# schema_v1.net
KiCad netlist of a schematic drawn in EAGLE
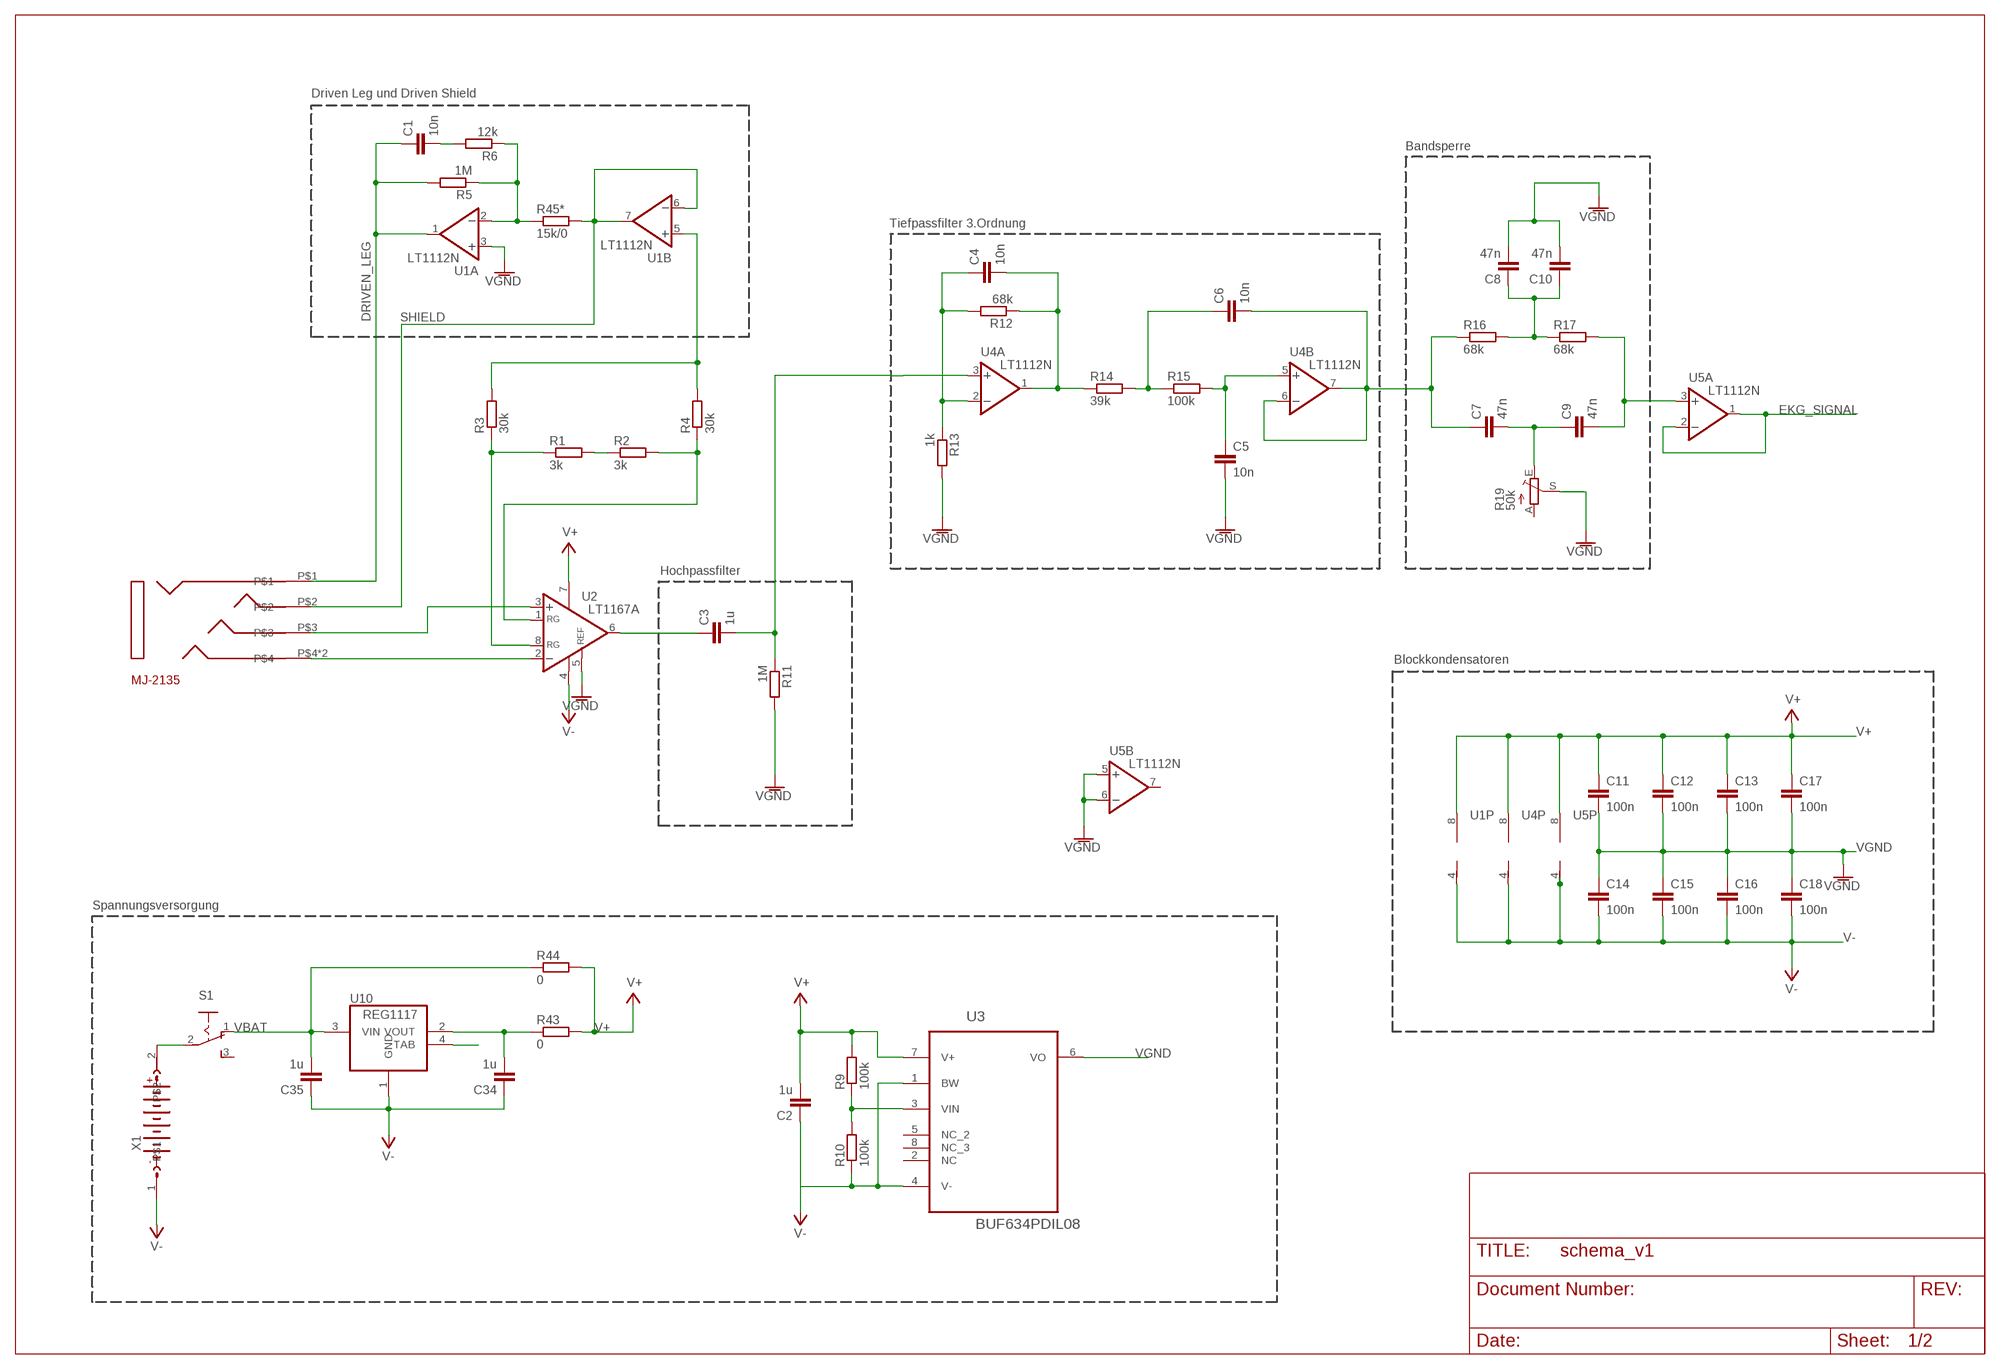
[diagram p0: schematic, sheet 1]
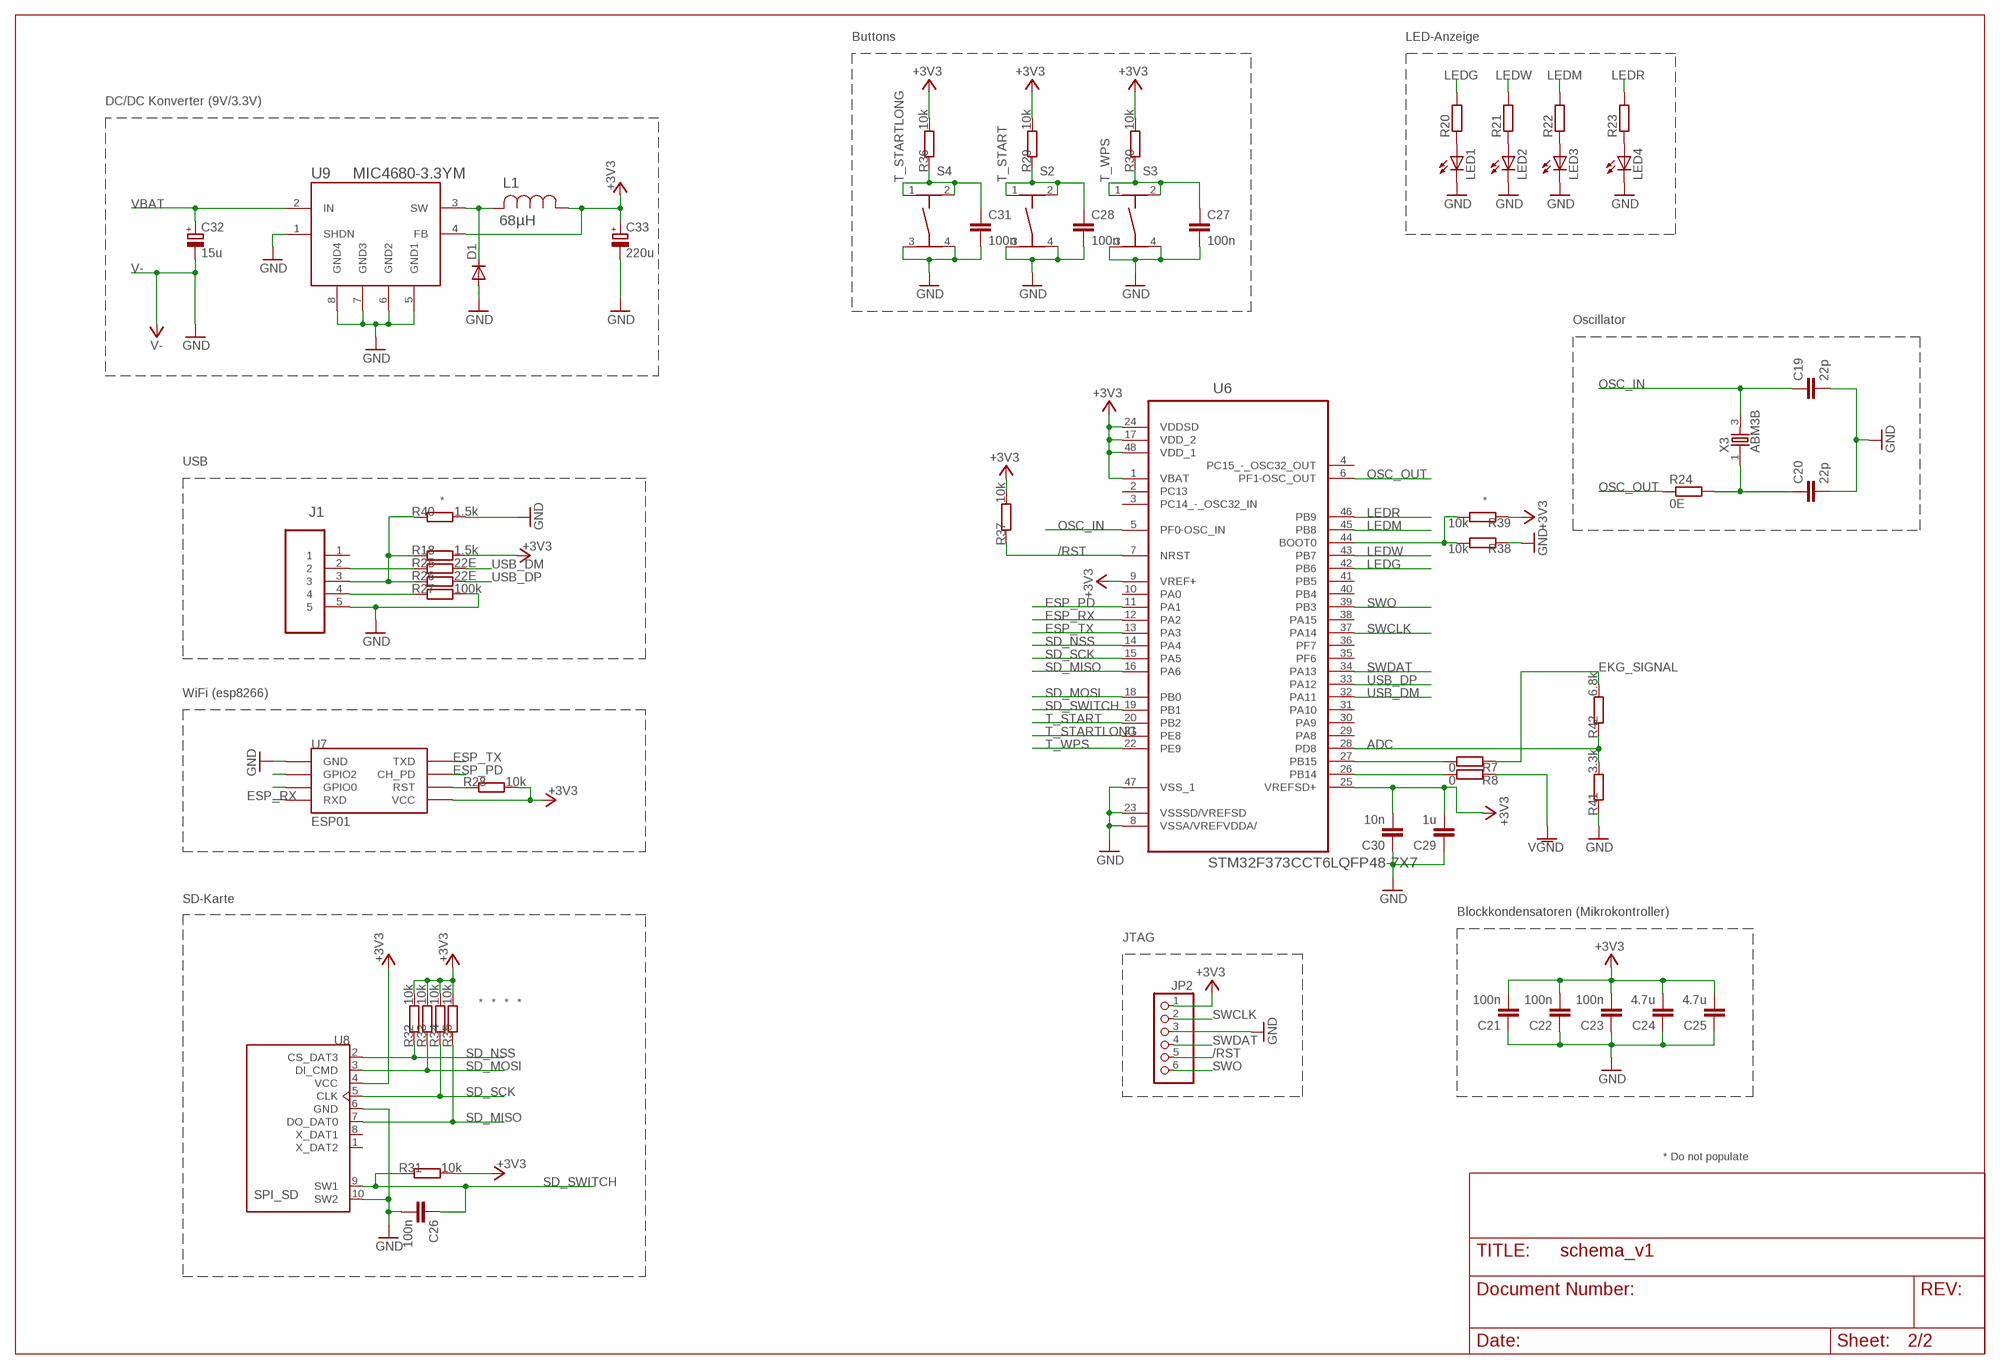
[diagram p1: schematic, sheet 2]

(export (version "E")
  (design (tool "Eeschema 10.0.6"))
  (components
    (comp (ref "C1")
      (value "10n")
      (footprint "eagle-import:C0805")
      (libsource (lib "eagle-import") (part "C-EUC0805"))
    )
    (comp (ref "C2")
      (value "1u")
      (footprint "eagle-import:C0805")
      (libsource (lib "eagle-import") (part "C-EUC0805"))
    )
    (comp (ref "C3")
      (value "1u")
      (footprint "eagle-import:C0805")
      (libsource (lib "eagle-import") (part "C-EUC0805"))
    )
    (comp (ref "C4")
      (value "10n")
      (footprint "eagle-import:C0805")
      (libsource (lib "eagle-import") (part "C-EUC0805"))
    )
    (comp (ref "C5")
      (value "10n")
      (footprint "eagle-import:C0805")
      (libsource (lib "eagle-import") (part "C-EUC0805"))
    )
    (comp (ref "C6")
      (value "10n")
      (footprint "eagle-import:C0805")
      (libsource (lib "eagle-import") (part "C-EUC0805"))
    )
    (comp (ref "C7")
      (value "47n")
      (footprint "eagle-import:C0805")
      (libsource (lib "eagle-import") (part "C-EUC0805"))
    )
    (comp (ref "C8")
      (value "47n")
      (footprint "eagle-import:C0805")
      (libsource (lib "eagle-import") (part "C-EUC0805"))
    )
    (comp (ref "C9")
      (value "47n")
      (footprint "eagle-import:C0805")
      (libsource (lib "eagle-import") (part "C-EUC0805"))
    )
    (comp (ref "C10")
      (value "47n")
      (footprint "eagle-import:C0805")
      (libsource (lib "eagle-import") (part "C-EUC0805"))
    )
    (comp (ref "C11")
      (value "100n")
      (footprint "eagle-import:C0805")
      (libsource (lib "eagle-import") (part "C-EUC0805"))
    )
    (comp (ref "C12")
      (value "100n")
      (footprint "eagle-import:C0805")
      (libsource (lib "eagle-import") (part "C-EUC0805"))
    )
    (comp (ref "C13")
      (value "100n")
      (footprint "eagle-import:C0805")
      (libsource (lib "eagle-import") (part "C-EUC0805"))
    )
    (comp (ref "C14")
      (value "100n")
      (footprint "eagle-import:C0805")
      (libsource (lib "eagle-import") (part "C-EUC0805"))
    )
    (comp (ref "C15")
      (value "100n")
      (footprint "eagle-import:C0805")
      (libsource (lib "eagle-import") (part "C-EUC0805"))
    )
    (comp (ref "C16")
      (value "100n")
      (footprint "eagle-import:C0805")
      (libsource (lib "eagle-import") (part "C-EUC0805"))
    )
    (comp (ref "C17")
      (value "100n")
      (footprint "eagle-import:C0805")
      (libsource (lib "eagle-import") (part "C-EUC0805"))
    )
    (comp (ref "C18")
      (value "100n")
      (footprint "eagle-import:C0805")
      (libsource (lib "eagle-import") (part "C-EUC0805"))
    )
    (comp (ref "C34")
      (value "1u")
      (footprint "eagle-import:C0805")
      (libsource (lib "eagle-import") (part "C-EUC0805"))
    )
    (comp (ref "C35")
      (value "1u")
      (footprint "eagle-import:C0805")
      (libsource (lib "eagle-import") (part "C-EUC0805"))
    )
    (comp (ref "R1")
      (value "3k")
      (footprint "eagle-import:M0805")
      (libsource (lib "eagle-import") (part "R-EU_M0805"))
    )
    (comp (ref "R2")
      (value "3k")
      (footprint "eagle-import:M0805")
      (libsource (lib "eagle-import") (part "R-EU_M0805"))
    )
    (comp (ref "R3")
      (value "30k")
      (footprint "eagle-import:M0805")
      (libsource (lib "eagle-import") (part "R-EU_M0805"))
    )
    (comp (ref "R4")
      (value "30k")
      (footprint "eagle-import:M0805")
      (libsource (lib "eagle-import") (part "R-EU_M0805"))
    )
    (comp (ref "R5")
      (value "1M")
      (footprint "eagle-import:M0805")
      (libsource (lib "eagle-import") (part "R-EU_M0805"))
    )
    (comp (ref "R6")
      (value "12k")
      (footprint "eagle-import:M0805")
      (libsource (lib "eagle-import") (part "R-EU_M0805"))
    )
    (comp (ref "R9")
      (value "100k")
      (footprint "eagle-import:M0805")
      (libsource (lib "eagle-import") (part "R-EU_M0805"))
    )
    (comp (ref "R10")
      (value "100k")
      (footprint "eagle-import:M0805")
      (libsource (lib "eagle-import") (part "R-EU_M0805"))
    )
    (comp (ref "R11")
      (value "1M")
      (footprint "eagle-import:M0805")
      (libsource (lib "eagle-import") (part "R-EU_M0805"))
    )
    (comp (ref "R12")
      (value "68k")
      (footprint "eagle-import:M0805")
      (libsource (lib "eagle-import") (part "R-EU_M0805"))
    )
    (comp (ref "R13")
      (value "1k")
      (footprint "eagle-import:M0805")
      (libsource (lib "eagle-import") (part "R-EU_M0805"))
    )
    (comp (ref "R14")
      (value "39k")
      (footprint "eagle-import:M0805")
      (libsource (lib "eagle-import") (part "R-EU_M0805"))
    )
    (comp (ref "R15")
      (value "100k")
      (footprint "eagle-import:M0805")
      (libsource (lib "eagle-import") (part "R-EU_M0805"))
    )
    (comp (ref "R16")
      (value "68k")
      (footprint "eagle-import:M0805")
      (libsource (lib "eagle-import") (part "R-EU_M0805"))
    )
    (comp (ref "R17")
      (value "68k")
      (footprint "eagle-import:M0805")
      (libsource (lib "eagle-import") (part "R-EU_M0805"))
    )
    (comp (ref "R19")
      (value "50k")
      (footprint "eagle-import:B25P")
      (libsource (lib "eagle-import") (part "TRIM_EU-B25P"))
    )
    (comp (ref "R43")
      (value "0")
      (footprint "eagle-import:M0805")
      (libsource (lib "eagle-import") (part "R-EU_M0805"))
    )
    (comp (ref "R44")
      (value "0")
      (footprint "eagle-import:M0805")
      (libsource (lib "eagle-import") (part "R-EU_M0805"))
    )
    (comp (ref "R45*")
      (value "15k/0")
      (footprint "eagle-import:R0805")
      (libsource (lib "eagle-import") (part "R-EU_R0805"))
    )
    (comp (ref "S1")
      (value "255SB")
      (footprint "eagle-import:255SB")
      (libsource (lib "eagle-import") (part "255SB"))
    )
    (comp (ref "U1")
      (value "LT1112N")
      (footprint "eagle-import:DIL08")
      (libsource (lib "eagle-import") (part "LT1112N"))
    )
    (comp (ref "U2")
      (value "LT1167A")
      (footprint "eagle-import:DIL08")
      (libsource (lib "eagle-import") (part "LT1167A"))
    )
    (comp (ref "U3")
      (value "BUF634PDIL08")
      (footprint "eagle-import:DIL08")
      (libsource (lib "eagle-import") (part "BUF634PDIL08"))
    )
    (comp (ref "U4")
      (value "LT1112N")
      (footprint "eagle-import:DIL08")
      (libsource (lib "eagle-import") (part "LT1112N"))
    )
    (comp (ref "U5")
      (value "LT1112N")
      (footprint "eagle-import:DIL08")
      (libsource (lib "eagle-import") (part "LT1112N"))
    )
    (comp (ref "U10")
      (value "REG1117")
      (footprint "eagle-import:SOT223")
      (libsource (lib "eagle-import") (part "REG1117"))
    )
    (comp (ref "X1")
      (value "BATTERY")
      (footprint "eagle-import:1X02")
      (libsource (lib "eagle-import") (part "BATTERY"))
    )
    (comp (ref "X2")
      (value "MJ2135")
      (footprint "eagle-import:MJ-2135")
      (libsource (lib "eagle-import") (part "MJ2135"))
    )
    (comp (ref "C19")
      (value "22p")
      (footprint "eagle-import:C0805")
      (libsource (lib "eagle-import") (part "C-EUC0805"))
    )
    (comp (ref "C20")
      (value "22p")
      (footprint "eagle-import:C0805")
      (libsource (lib "eagle-import") (part "C-EUC0805"))
    )
    (comp (ref "C21")
      (value "100n")
      (footprint "eagle-import:C0805")
      (libsource (lib "eagle-import") (part "C-EUC0805"))
    )
    (comp (ref "C22")
      (value "100n")
      (footprint "eagle-import:C0805")
      (libsource (lib "eagle-import") (part "C-EUC0805"))
    )
    (comp (ref "C23")
      (value "100n")
      (footprint "eagle-import:C0805")
      (libsource (lib "eagle-import") (part "C-EUC0805"))
    )
    (comp (ref "C24")
      (value "4.7u")
      (footprint "eagle-import:C0805")
      (libsource (lib "eagle-import") (part "C-EUC0805"))
    )
    (comp (ref "C25")
      (value "4.7u")
      (footprint "eagle-import:C0805")
      (libsource (lib "eagle-import") (part "C-EUC0805"))
    )
    (comp (ref "C26")
      (value "100n")
      (footprint "eagle-import:C0805")
      (libsource (lib "eagle-import") (part "C-EUC0805"))
    )
    (comp (ref "C27")
      (value "100n")
      (footprint "eagle-import:C0805")
      (libsource (lib "eagle-import") (part "C-EUC0805"))
    )
    (comp (ref "C28")
      (value "100n")
      (footprint "eagle-import:C0805")
      (libsource (lib "eagle-import") (part "C-EUC0805"))
    )
    (comp (ref "C29")
      (value "1u")
      (footprint "eagle-import:C0805")
      (libsource (lib "eagle-import") (part "C-EUC0805"))
    )
    (comp (ref "C30")
      (value "10n")
      (footprint "eagle-import:C0805")
      (libsource (lib "eagle-import") (part "C-EUC0805"))
    )
    (comp (ref "C31")
      (value "100n")
      (footprint "eagle-import:C0805")
      (libsource (lib "eagle-import") (part "C-EUC0805"))
    )
    (comp (ref "C32")
      (value "15u")
      (footprint "eagle-import:SMC_B")
      (libsource (lib "eagle-import") (part "CPOL-EUSMCB"))
    )
    (comp (ref "C33")
      (value "220u")
      (footprint "eagle-import:SMC_E")
      (libsource (lib "eagle-import") (part "CPOL-EUSMCE"))
    )
    (comp (ref "D1")
      (value "DIODE-DO214AC")
      (footprint "eagle-import:DO214AC")
      (libsource (lib "eagle-import") (part "DIODE-DO214AC"))
    )
    (comp (ref "J1")
      (value "47346-0001")
      (footprint "eagle-import:MOLEX_47346-0001")
      (libsource (lib "eagle-import") (part "47346-0001"))
    )
    (comp (ref "JP2")
      (value "PINHD-1X6")
      (footprint "eagle-import:1X06")
      (libsource (lib "eagle-import") (part "PINHD-1X6"))
    )
    (comp (ref "L1")
      (value "68µH")
      (footprint "eagle-import:INDM1410X600N")
      (fields (field (name "MPN") "UP2B-680-R") (field (name "TOLERANCE") "±20%"))
      (libsource (lib "eagle-import") (part "UP2B-680-R"))
    )
    (comp (ref "LED1")
      (value "LED3MM")
      (footprint "eagle-import:LED3MM")
      (libsource (lib "eagle-import") (part "LED3MM"))
    )
    (comp (ref "LED2")
      (value "LED3MM")
      (footprint "eagle-import:LED3MM")
      (libsource (lib "eagle-import") (part "LED3MM"))
    )
    (comp (ref "LED3")
      (value "LED3MM")
      (footprint "eagle-import:LED3MM")
      (libsource (lib "eagle-import") (part "LED3MM"))
    )
    (comp (ref "LED4")
      (value "LED3MM")
      (footprint "eagle-import:LED3MM")
      (libsource (lib "eagle-import") (part "LED3MM"))
    )
    (comp (ref "R7")
      (value "0")
      (footprint "eagle-import:R0805")
      (libsource (lib "eagle-import") (part "R-EU_R0805"))
    )
    (comp (ref "R8")
      (value "0")
      (footprint "eagle-import:R0805")
      (libsource (lib "eagle-import") (part "R-EU_R0805"))
    )
    (comp (ref "R18")
      (value "1.5k")
      (footprint "eagle-import:R0805")
      (libsource (lib "eagle-import") (part "R-EU_R0805"))
    )
    (comp (ref "R20")
      (value "R-EU_R0805")
      (footprint "eagle-import:R0805")
      (libsource (lib "eagle-import") (part "R-EU_R0805"))
    )
    (comp (ref "R21")
      (value "R-EU_R0805")
      (footprint "eagle-import:R0805")
      (libsource (lib "eagle-import") (part "R-EU_R0805"))
    )
    (comp (ref "R22")
      (value "R-EU_R0805")
      (footprint "eagle-import:R0805")
      (libsource (lib "eagle-import") (part "R-EU_R0805"))
    )
    (comp (ref "R23")
      (value "R-EU_R0805")
      (footprint "eagle-import:R0805")
      (libsource (lib "eagle-import") (part "R-EU_R0805"))
    )
    (comp (ref "R24")
      (value "0E")
      (footprint "eagle-import:R0805")
      (libsource (lib "eagle-import") (part "R-EU_R0805"))
    )
    (comp (ref "R25")
      (value "22E")
      (footprint "eagle-import:R0805")
      (libsource (lib "eagle-import") (part "R-EU_R0805"))
    )
    (comp (ref "R26")
      (value "22E")
      (footprint "eagle-import:R0805")
      (libsource (lib "eagle-import") (part "R-EU_R0805"))
    )
    (comp (ref "R27")
      (value "100k")
      (footprint "eagle-import:R0805")
      (libsource (lib "eagle-import") (part "R-EU_R0805"))
    )
    (comp (ref "R28")
      (value "10k")
      (footprint "eagle-import:R0805")
      (libsource (lib "eagle-import") (part "R-EU_R0805"))
    )
    (comp (ref "R29")
      (value "10k")
      (footprint "eagle-import:R0805")
      (libsource (lib "eagle-import") (part "R-EU_R0805"))
    )
    (comp (ref "R30")
      (value "10k")
      (footprint "eagle-import:R0805")
      (libsource (lib "eagle-import") (part "R-EU_R0805"))
    )
    (comp (ref "R31")
      (value "10k")
      (footprint "eagle-import:R0805")
      (libsource (lib "eagle-import") (part "R-EU_R0805"))
    )
    (comp (ref "R32")
      (value "10k")
      (footprint "eagle-import:R0805")
      (libsource (lib "eagle-import") (part "R-EU_R0805"))
    )
    (comp (ref "R33")
      (value "10k")
      (footprint "eagle-import:R0805")
      (libsource (lib "eagle-import") (part "R-EU_R0805"))
    )
    (comp (ref "R34")
      (value "10k")
      (footprint "eagle-import:R0805")
      (libsource (lib "eagle-import") (part "R-EU_R0805"))
    )
    (comp (ref "R35")
      (value "10k")
      (footprint "eagle-import:R0805")
      (libsource (lib "eagle-import") (part "R-EU_R0805"))
    )
    (comp (ref "R36")
      (value "10k")
      (footprint "eagle-import:R0805")
      (libsource (lib "eagle-import") (part "R-EU_R0805"))
    )
    (comp (ref "R37")
      (value "10k")
      (footprint "eagle-import:R0805")
      (libsource (lib "eagle-import") (part "R-EU_R0805"))
    )
    (comp (ref "R38")
      (value "10k")
      (footprint "eagle-import:R0805")
      (libsource (lib "eagle-import") (part "R-EU_R0805"))
    )
    (comp (ref "R39")
      (value "10k")
      (footprint "eagle-import:R0805")
      (libsource (lib "eagle-import") (part "R-EU_R0805"))
    )
    (comp (ref "R40")
      (value "1.5k")
      (footprint "eagle-import:R0805")
      (libsource (lib "eagle-import") (part "R-EU_R0805"))
    )
    (comp (ref "R41")
      (value "3.3k")
      (footprint "eagle-import:R0805")
      (libsource (lib "eagle-import") (part "R-EU_R0805"))
    )
    (comp (ref "R42")
      (value "6.8k")
      (footprint "eagle-import:R0805")
      (libsource (lib "eagle-import") (part "R-EU_R0805"))
    )
    (comp (ref "S2")
      (value "TASTER-9314_SMD")
      (footprint "eagle-import:TASTER-9314_SMD")
      (libsource (lib "eagle-import") (part "TASTER-9314_SMD"))
    )
    (comp (ref "S3")
      (value "TASTER-9314_SMD")
      (footprint "eagle-import:TASTER-9314_SMD")
      (libsource (lib "eagle-import") (part "TASTER-9314_SMD"))
    )
    (comp (ref "S4")
      (value "TASTER-9314_SMD")
      (footprint "eagle-import:TASTER-9314_SMD")
      (libsource (lib "eagle-import") (part "TASTER-9314_SMD"))
    )
    (comp (ref "U6")
      (value "STM32F373CCT6LQFP48-7X7")
      (footprint "eagle-import:LQFP48-7X7")
      (libsource (lib "eagle-import") (part "STM32F373CCT6LQFP48-7X7"))
    )
    (comp (ref "U7")
      (value "ESP01")
      (footprint "eagle-import:ESP01")
      (libsource (lib "eagle-import") (part "ESP01"))
    )
    (comp (ref "U8")
      (value "MICROSD")
      (footprint "eagle-import:SD-503398-003")
      (libsource (lib "eagle-import") (part "MICROSD"))
    )
    (comp (ref "U9")
      (value "MIC4680-3.3YM")
      (footprint "eagle-import:SOIC8")
      (fields (field (name "MF") "MICROCHIP"))
      (libsource (lib "eagle-import") (part "MIC4680-3.3YM"))
    )
    (comp (ref "X3")
      (value "ABM3B")
      (footprint "eagle-import:IQG5032B")
      (libsource (lib "eagle-import") (part "ABM3B"))
    )
  )
  (nets
    (net (code "1") (name "+3V3") (class "Default")
      (node (ref "C21") (pin "2") (pinfunction "2_2") (pintype "passive"))
      (node (ref "C22") (pin "2") (pinfunction "2_2") (pintype "passive"))
      (node (ref "C23") (pin "2") (pinfunction "2_2") (pintype "passive"))
      (node (ref "C24") (pin "2") (pinfunction "2_2") (pintype "passive"))
      (node (ref "C25") (pin "2") (pinfunction "2_2") (pintype "passive"))
      (node (ref "C29") (pin "2") (pinfunction "2_2") (pintype "passive"))
      (node (ref "C30") (pin "2") (pinfunction "2_2") (pintype "passive"))
      (node (ref "C33") (pin "+") (pinfunction "+_+") (pintype "passive"))
      (node (ref "JP2") (pin "1") (pinfunction "1_1") (pintype "passive"))
      (node (ref "L1") (pin "1") (pinfunction "1_1") (pintype "passive"))
      (node (ref "R18") (pin "2") (pinfunction "2_2") (pintype "passive"))
      (node (ref "R28") (pin "2") (pinfunction "2_2") (pintype "passive"))
      (node (ref "R29") (pin "2") (pinfunction "2_2") (pintype "passive"))
      (node (ref "R30") (pin "2") (pinfunction "2_2") (pintype "passive"))
      (node (ref "R31") (pin "2") (pinfunction "2_2") (pintype "passive"))
      (node (ref "R32") (pin "2") (pinfunction "2_2") (pintype "passive"))
      (node (ref "R33") (pin "2") (pinfunction "2_2") (pintype "passive"))
      (node (ref "R34") (pin "2") (pinfunction "2_2") (pintype "passive"))
      (node (ref "R35") (pin "2") (pinfunction "2_2") (pintype "passive"))
      (node (ref "R36") (pin "2") (pinfunction "2_2") (pintype "passive"))
      (node (ref "R37") (pin "2") (pinfunction "2_2") (pintype "passive"))
      (node (ref "R39") (pin "1") (pinfunction "1_1") (pintype "passive"))
      (node (ref "U6") (pin "1") (pinfunction "VBAT_1") (pintype "passive"))
      (node (ref "U6") (pin "17") (pinfunction "VDD_2_17") (pintype "power_in"))
      (node (ref "U6") (pin "24") (pinfunction "VDDSD_24") (pintype "power_in"))
      (node (ref "U6") (pin "25") (pinfunction "VREFSD+_25") (pintype "passive"))
      (node (ref "U6") (pin "48") (pinfunction "VDD_1_48") (pintype "power_in"))
      (node (ref "U6") (pin "9") (pinfunction "VREF+_9") (pintype "passive"))
      (node (ref "U7") (pin "VCC") (pinfunction "VCC_VCC") (pintype "bidirectional"))
      (node (ref "U8") (pin "4") (pinfunction "VCC_4") (pintype "power_in"))
      (node (ref "U9") (pin "4") (pinfunction "FB_4") (pintype "bidirectional"))
    )
    (net (code "2") (name "ADC") (class "Default")
      (node (ref "R41") (pin "2") (pinfunction "2_2") (pintype "passive"))
      (node (ref "R42") (pin "1") (pinfunction "1_1") (pintype "passive"))
      (node (ref "U6") (pin "28") (pinfunction "PD8_28") (pintype "bidirectional"))
    )
    (net (code "3") (name "DRIVEN_LEG") (class "Default")
      (node (ref "C1") (pin "1") (pinfunction "1_1") (pintype "passive"))
      (node (ref "R5") (pin "2") (pinfunction "2_2") (pintype "passive"))
      (node (ref "U1") (pin "1") (pinfunction "OUT_1") (pintype "output"))
      (node (ref "X2") (pin "P$1") (pinfunction "P$1_P$1") (pintype "bidirectional"))
    )
    (net (code "4") (name "EKG_SIGNAL") (class "Default")
      (node (ref "R42") (pin "2") (pinfunction "2_2") (pintype "passive"))
      (node (ref "R7") (pin "1") (pinfunction "1_1") (pintype "passive"))
      (node (ref "U5") (pin "1") (pinfunction "OUT_1") (pintype "output"))
      (node (ref "U5") (pin "2") (pinfunction "-IN_2") (pintype "input"))
    )
    (net (code "5") (name "ESP_PD") (class "Default")
      (node (ref "U6") (pin "11") (pinfunction "PA1_11") (pintype "bidirectional"))
      (node (ref "U7") (pin "CH_PD") (pinfunction "CH_PD_CH_PD") (pintype "bidirectional"))
    )
    (net (code "6") (name "ESP_RX") (class "Default")
      (node (ref "U6") (pin "12") (pinfunction "PA2_12") (pintype "bidirectional"))
      (node (ref "U7") (pin "RX") (pinfunction "RXD_RX") (pintype "bidirectional"))
    )
    (net (code "7") (name "ESP_TX") (class "Default")
      (node (ref "U6") (pin "13") (pinfunction "PA3_13") (pintype "bidirectional"))
      (node (ref "U7") (pin "TX") (pinfunction "TXD_TX") (pintype "bidirectional"))
    )
    (net (code "8") (name "LEDG") (class "Default")
      (node (ref "R20") (pin "2") (pinfunction "2_2") (pintype "passive"))
      (node (ref "U6") (pin "42") (pinfunction "PB6_42") (pintype "bidirectional"))
    )
    (net (code "9") (name "LEDM") (class "Default")
      (node (ref "R22") (pin "2") (pinfunction "2_2") (pintype "passive"))
      (node (ref "U6") (pin "45") (pinfunction "PB8_45") (pintype "bidirectional"))
    )
    (net (code "10") (name "LEDR") (class "Default")
      (node (ref "R23") (pin "2") (pinfunction "2_2") (pintype "passive"))
      (node (ref "U6") (pin "46") (pinfunction "PB9_46") (pintype "bidirectional"))
    )
    (net (code "11") (name "LEDW") (class "Default")
      (node (ref "R21") (pin "2") (pinfunction "2_2") (pintype "passive"))
      (node (ref "U6") (pin "43") (pinfunction "PB7_43") (pintype "bidirectional"))
    )
    (net (code "12") (name "Net-(C1-Pad2)") (class "Default")
      (node (ref "C1") (pin "2") (pinfunction "2_2") (pintype "passive"))
      (node (ref "R6") (pin "2") (pinfunction "2_2") (pintype "passive"))
    )
    (net (code "13") (name "Net-(C6-Pad1)") (class "Default")
      (node (ref "C6") (pin "1") (pinfunction "1_1") (pintype "passive"))
      (node (ref "R14") (pin "2") (pinfunction "2_2") (pintype "passive"))
      (node (ref "R15") (pin "1") (pinfunction "1_1") (pintype "passive"))
    )
    (net (code "14") (name "Net-(C7-Pad2)") (class "Default")
      (node (ref "C7") (pin "2") (pinfunction "2_2") (pintype "passive"))
      (node (ref "C9") (pin "1") (pinfunction "1_1") (pintype "passive"))
      (node (ref "R19") (pin "E") (pinfunction "E_E") (pintype "passive"))
    )
    (net (code "15") (name "Net-(C10-Pad1)") (class "Default")
      (node (ref "C10") (pin "1") (pinfunction "1_1") (pintype "passive"))
      (node (ref "C8") (pin "1") (pinfunction "1_1") (pintype "passive"))
      (node (ref "R16") (pin "2") (pinfunction "2_2") (pintype "passive"))
      (node (ref "R17") (pin "1") (pinfunction "1_1") (pintype "passive"))
    )
    (net (code "16") (name "Net-(C20-Pad1)") (class "Default")
      (node (ref "C20") (pin "1") (pinfunction "1_1") (pintype "passive"))
      (node (ref "R24") (pin "2") (pinfunction "2_2") (pintype "passive"))
      (node (ref "X3") (pin "1") (pinfunction "1_1") (pintype "passive"))
    )
    (net (code "17") (name "Net-(J1-Pad2)") (class "Default")
      (node (ref "J1") (pin "2") (pinfunction "2_2") (pintype "input"))
      (node (ref "R25") (pin "1") (pinfunction "1_1") (pintype "passive"))
    )
    (net (code "18") (name "Net-(J1-Pad3)") (class "Default")
      (node (ref "J1") (pin "3") (pinfunction "3_3") (pintype "input"))
      (node (ref "R18") (pin "1") (pinfunction "1_1") (pintype "passive"))
      (node (ref "R26") (pin "1") (pinfunction "1_1") (pintype "passive"))
      (node (ref "R40") (pin "1") (pinfunction "1_1") (pintype "passive"))
    )
    (net (code "19") (name "Net-(J1-Pad4)") (class "Default")
      (node (ref "J1") (pin "4") (pinfunction "4_4") (pintype "input"))
      (node (ref "R27") (pin "1") (pinfunction "1_1") (pintype "passive"))
    )
    (net (code "20") (name "Net-(LED1-PadA)") (class "Default")
      (node (ref "LED1") (pin "A") (pinfunction "A_A") (pintype "passive"))
      (node (ref "R20") (pin "1") (pinfunction "1_1") (pintype "passive"))
    )
    (net (code "21") (name "Net-(LED2-PadA)") (class "Default")
      (node (ref "LED2") (pin "A") (pinfunction "A_A") (pintype "passive"))
      (node (ref "R21") (pin "1") (pinfunction "1_1") (pintype "passive"))
    )
    (net (code "22") (name "Net-(LED3-PadA)") (class "Default")
      (node (ref "LED3") (pin "A") (pinfunction "A_A") (pintype "passive"))
      (node (ref "R22") (pin "1") (pinfunction "1_1") (pintype "passive"))
    )
    (net (code "23") (name "Net-(LED4-PadA)") (class "Default")
      (node (ref "LED4") (pin "A") (pinfunction "A_A") (pintype "passive"))
      (node (ref "R23") (pin "1") (pinfunction "1_1") (pintype "passive"))
    )
    (net (code "24") (name "Net-(R1-Pad1)") (class "Default")
      (node (ref "R1") (pin "1") (pinfunction "1_1") (pintype "passive"))
      (node (ref "R3") (pin "1") (pinfunction "1_1") (pintype "passive"))
      (node (ref "U2") (pin "8") (pinfunction "RG_8") (pintype "input"))
    )
    (net (code "25") (name "Net-(R1-Pad2)") (class "Default")
      (node (ref "R1") (pin "2") (pinfunction "2_2") (pintype "passive"))
      (node (ref "R2") (pin "1") (pinfunction "1_1") (pintype "passive"))
    )
    (net (code "26") (name "Net-(R2-Pad2)") (class "Default")
      (node (ref "R2") (pin "2") (pinfunction "2_2") (pintype "passive"))
      (node (ref "R4") (pin "1") (pinfunction "1_1") (pintype "passive"))
      (node (ref "U2") (pin "1") (pinfunction "RG_1") (pintype "input"))
    )
    (net (code "27") (name "Net-(R28-Pad1)") (class "Default")
      (node (ref "R28") (pin "1") (pinfunction "1_1") (pintype "passive"))
      (node (ref "U7") (pin "RST") (pinfunction "RST_RST") (pintype "bidirectional"))
    )
    (net (code "28") (name "Net-(S1-P)") (class "Default")
      (node (ref "S1") (pin "2") (pinfunction "P_2") (pintype "passive"))
      (node (ref "X1") (pin "2") (pinfunction "P$2_2") (pintype "bidirectional"))
    )
    (net (code "29") (name "Net-(U1A--IN)") (class "Default")
      (node (ref "R45*") (pin "1") (pinfunction "1_1") (pintype "passive"))
      (node (ref "R5") (pin "1") (pinfunction "1_1") (pintype "passive"))
      (node (ref "R6") (pin "1") (pinfunction "1_1") (pintype "passive"))
      (node (ref "U1") (pin "2") (pinfunction "-IN_2") (pintype "input"))
    )
    (net (code "30") (name "Net-(U1B-+IN)") (class "Default")
      (node (ref "R3") (pin "2") (pinfunction "2_2") (pintype "passive"))
      (node (ref "R4") (pin "2") (pinfunction "2_2") (pintype "passive"))
      (node (ref "U1") (pin "5") (pinfunction "+IN_5") (pintype "input"))
    )
    (net (code "31") (name "Net-(U2-+IN)") (class "Default")
      (node (ref "U2") (pin "3") (pinfunction "+IN_3") (pintype "input"))
      (node (ref "X2") (pin "P$3") (pinfunction "P$3_P$3") (pintype "bidirectional"))
    )
    (net (code "32") (name "Net-(U2--IN)") (class "Default")
      (node (ref "U2") (pin "2") (pinfunction "-IN_2") (pintype "input"))
      (node (ref "X2") (pin "P$4") (pinfunction "P$4_P$4") (pintype "bidirectional"))
      (node (ref "X2") (pin "P$5") (pinfunction "P$4_P$5") (pintype "bidirectional"))
    )
    (net (code "33") (name "Net-(U2-OUT)") (class "Default")
      (node (ref "C3") (pin "1") (pinfunction "1_1") (pintype "passive"))
      (node (ref "U2") (pin "6") (pinfunction "OUT_6") (pintype "output"))
    )
    (net (code "34") (name "Net-(U3-VIN)") (class "Default")
      (node (ref "R10") (pin "2") (pinfunction "2_2") (pintype "passive"))
      (node (ref "R9") (pin "1") (pinfunction "1_1") (pintype "passive"))
      (node (ref "U3") (pin "3") (pinfunction "VIN_3") (pintype "input"))
    )
    (net (code "35") (name "Net-(U4A-+IN)") (class "Default")
      (node (ref "C3") (pin "2") (pinfunction "2_2") (pintype "passive"))
      (node (ref "R11") (pin "1") (pinfunction "1_1") (pintype "passive"))
      (node (ref "U4") (pin "3") (pinfunction "+IN_3") (pintype "input"))
    )
    (net (code "36") (name "Net-(U4A--IN)") (class "Default")
      (node (ref "C4") (pin "1") (pinfunction "1_1") (pintype "passive"))
      (node (ref "R12") (pin "2") (pinfunction "2_2") (pintype "passive"))
      (node (ref "R13") (pin "1") (pinfunction "1_1") (pintype "passive"))
      (node (ref "U4") (pin "2") (pinfunction "-IN_2") (pintype "input"))
    )
    (net (code "37") (name "Net-(U4A-OUT)") (class "Default")
      (node (ref "C4") (pin "2") (pinfunction "2_2") (pintype "passive"))
      (node (ref "R12") (pin "1") (pinfunction "1_1") (pintype "passive"))
      (node (ref "R14") (pin "1") (pinfunction "1_1") (pintype "passive"))
      (node (ref "U4") (pin "1") (pinfunction "OUT_1") (pintype "output"))
    )
    (net (code "38") (name "Net-(U4B-+IN)") (class "Default")
      (node (ref "C5") (pin "1") (pinfunction "1_1") (pintype "passive"))
      (node (ref "R15") (pin "2") (pinfunction "2_2") (pintype "passive"))
      (node (ref "U4") (pin "5") (pinfunction "+IN_5") (pintype "input"))
    )
    (net (code "39") (name "Net-(U4B--IN)") (class "Default")
      (node (ref "C6") (pin "2") (pinfunction "2_2") (pintype "passive"))
      (node (ref "C7") (pin "1") (pinfunction "1_1") (pintype "passive"))
      (node (ref "R16") (pin "1") (pinfunction "1_1") (pintype "passive"))
      (node (ref "U4") (pin "6") (pinfunction "-IN_6") (pintype "input"))
      (node (ref "U4") (pin "7") (pinfunction "OUT_7") (pintype "output"))
    )
    (net (code "40") (name "Net-(U5A-+IN)") (class "Default")
      (node (ref "C9") (pin "2") (pinfunction "2_2") (pintype "passive"))
      (node (ref "R17") (pin "2") (pinfunction "2_2") (pintype "passive"))
      (node (ref "U5") (pin "3") (pinfunction "+IN_3") (pintype "input"))
    )
    (net (code "41") (name "Net-(U6-BOOT0)") (class "Default")
      (node (ref "R38") (pin "2") (pinfunction "2_2") (pintype "passive"))
      (node (ref "R39") (pin "2") (pinfunction "2_2") (pintype "passive"))
      (node (ref "U6") (pin "44") (pinfunction "BOOT0_44") (pintype "passive"))
    )
    (net (code "42") (name "Net-(U6-PB14)") (class "Default")
      (node (ref "R8") (pin "2") (pinfunction "2_2") (pintype "passive"))
      (node (ref "U6") (pin "26") (pinfunction "PB14_26") (pintype "bidirectional"))
    )
    (net (code "43") (name "Net-(U6-PB15)") (class "Default")
      (node (ref "R7") (pin "2") (pinfunction "2_2") (pintype "passive"))
      (node (ref "U6") (pin "27") (pinfunction "PB15_27") (pintype "bidirectional"))
    )
    (net (code "44") (name "Net-(U9-SW)") (class "Default")
      (node (ref "D1") (pin "C") (pinfunction "C_C") (pintype "passive"))
      (node (ref "L1") (pin "2") (pinfunction "2_2") (pintype "passive"))
      (node (ref "U9") (pin "3") (pinfunction "SW_3") (pintype "bidirectional"))
    )
    (net (code "45") (name "Net-(U10-VOUT)") (class "Default")
      (node (ref "C34") (pin "2") (pinfunction "2_2") (pintype "passive"))
      (node (ref "R43") (pin "1") (pinfunction "1_1") (pintype "passive"))
      (node (ref "U10") (pin "2") (pinfunction "VOUT_2") (pintype "output"))
    )
    (net (code "46") (name "OSC_IN") (class "Default")
      (node (ref "C19") (pin "1") (pinfunction "1_1") (pintype "passive"))
      (node (ref "U6") (pin "5") (pinfunction "PF0-OSC_IN_5") (pintype "bidirectional"))
      (node (ref "X3") (pin "3") (pinfunction "2_3") (pintype "passive"))
    )
    (net (code "47") (name "OSC_OUT") (class "Default")
      (node (ref "R24") (pin "1") (pinfunction "1_1") (pintype "passive"))
      (node (ref "U6") (pin "6") (pinfunction "PF1-OSC_OUT_6") (pintype "bidirectional"))
    )
    (net (code "48") (name "SD_MISO") (class "Default")
      (node (ref "R35") (pin "1") (pinfunction "1_1") (pintype "passive"))
      (node (ref "U6") (pin "16") (pinfunction "PA6_16") (pintype "bidirectional"))
      (node (ref "U8") (pin "7") (pinfunction "DO_DAT0_7") (pintype "output"))
    )
    (net (code "49") (name "SD_MOSI") (class "Default")
      (node (ref "R33") (pin "1") (pinfunction "1_1") (pintype "passive"))
      (node (ref "U6") (pin "18") (pinfunction "PB0_18") (pintype "bidirectional"))
      (node (ref "U8") (pin "3") (pinfunction "DI_CMD_3") (pintype "input"))
    )
    (net (code "50") (name "SD_NSS") (class "Default")
      (node (ref "R32") (pin "1") (pinfunction "1_1") (pintype "passive"))
      (node (ref "U6") (pin "14") (pinfunction "PA4_14") (pintype "bidirectional"))
      (node (ref "U8") (pin "2") (pinfunction "CS_DAT3_2") (pintype "input"))
    )
    (net (code "51") (name "SD_SCK") (class "Default")
      (node (ref "R34") (pin "1") (pinfunction "1_1") (pintype "passive"))
      (node (ref "U6") (pin "15") (pinfunction "PA5_15") (pintype "bidirectional"))
      (node (ref "U8") (pin "5") (pinfunction "CLK_5") (pintype "input"))
    )
    (net (code "52") (name "SD_SWITCH") (class "Default")
      (node (ref "C26") (pin "1") (pinfunction "1_1") (pintype "passive"))
      (node (ref "R31") (pin "1") (pinfunction "1_1") (pintype "passive"))
      (node (ref "U6") (pin "19") (pinfunction "PB1_19") (pintype "bidirectional"))
      (node (ref "U8") (pin "9") (pinfunction "SW1_9") (pintype "output"))
    )
    (net (code "53") (name "SHIELD") (class "Default")
      (node (ref "R45*") (pin "2") (pinfunction "2_2") (pintype "passive"))
      (node (ref "U1") (pin "6") (pinfunction "-IN_6") (pintype "input"))
      (node (ref "U1") (pin "7") (pinfunction "OUT_7") (pintype "output"))
      (node (ref "X2") (pin "P$2") (pinfunction "P$2_P$2") (pintype "bidirectional"))
    )
    (net (code "54") (name "SWCLK") (class "Default")
      (node (ref "JP2") (pin "2") (pinfunction "2_2") (pintype "passive"))
      (node (ref "U6") (pin "37") (pinfunction "PA14_37") (pintype "bidirectional"))
    )
    (net (code "55") (name "SWDAT") (class "Default")
      (node (ref "JP2") (pin "4") (pinfunction "4_4") (pintype "passive"))
      (node (ref "U6") (pin "34") (pinfunction "PA13_34") (pintype "bidirectional"))
    )
    (net (code "56") (name "SWO") (class "Default")
      (node (ref "JP2") (pin "6") (pinfunction "6_6") (pintype "passive"))
      (node (ref "U6") (pin "39") (pinfunction "PB3_39") (pintype "bidirectional"))
    )
    (net (code "57") (name "T_START") (class "Default")
      (node (ref "C28") (pin "1") (pinfunction "1_1") (pintype "passive"))
      (node (ref "R29") (pin "1") (pinfunction "1_1") (pintype "passive"))
      (node (ref "S2") (pin "1") (pinfunction "1_1") (pintype "passive"))
      (node (ref "S2") (pin "2") (pinfunction "2_2") (pintype "passive"))
      (node (ref "U6") (pin "20") (pinfunction "PB2_20") (pintype "bidirectional"))
    )
    (net (code "58") (name "T_STARTLONG") (class "Default")
      (node (ref "C31") (pin "1") (pinfunction "1_1") (pintype "passive"))
      (node (ref "R36") (pin "1") (pinfunction "1_1") (pintype "passive"))
      (node (ref "S4") (pin "1") (pinfunction "1_1") (pintype "passive"))
      (node (ref "S4") (pin "2") (pinfunction "2_2") (pintype "passive"))
      (node (ref "U6") (pin "21") (pinfunction "PE8_21") (pintype "bidirectional"))
    )
    (net (code "59") (name "T_WPS") (class "Default")
      (node (ref "C27") (pin "1") (pinfunction "1_1") (pintype "passive"))
      (node (ref "R30") (pin "1") (pinfunction "1_1") (pintype "passive"))
      (node (ref "S3") (pin "1") (pinfunction "1_1") (pintype "passive"))
      (node (ref "S3") (pin "2") (pinfunction "2_2") (pintype "passive"))
      (node (ref "U6") (pin "22") (pinfunction "PE9_22") (pintype "bidirectional"))
    )
    (net (code "60") (name "USB_DM") (class "Default")
      (node (ref "R25") (pin "2") (pinfunction "2_2") (pintype "passive"))
      (node (ref "U6") (pin "32") (pinfunction "PA11_32") (pintype "bidirectional"))
    )
    (net (code "61") (name "USB_DP") (class "Default")
      (node (ref "R26") (pin "2") (pinfunction "2_2") (pintype "passive"))
      (node (ref "U6") (pin "33") (pinfunction "PA12_33") (pintype "bidirectional"))
    )
    (net (code "62") (name "V+") (class "Default")
      (node (ref "C11") (pin "1") (pinfunction "1_1") (pintype "passive"))
      (node (ref "C12") (pin "1") (pinfunction "1_1") (pintype "passive"))
      (node (ref "C13") (pin "1") (pinfunction "1_1") (pintype "passive"))
      (node (ref "C17") (pin "1") (pinfunction "1_1") (pintype "passive"))
      (node (ref "C2") (pin "2") (pinfunction "2_2") (pintype "passive"))
      (node (ref "R43") (pin "2") (pinfunction "2_2") (pintype "passive"))
      (node (ref "R44") (pin "2") (pinfunction "2_2") (pintype "passive"))
      (node (ref "R9") (pin "2") (pinfunction "2_2") (pintype "passive"))
      (node (ref "U1") (pin "8") (pinfunction "V+_8") (pintype "power_in"))
      (node (ref "U2") (pin "7") (pinfunction "V+_7") (pintype "power_in"))
      (node (ref "U3") (pin "7") (pinfunction "V+_7") (pintype "power_in"))
      (node (ref "U4") (pin "8") (pinfunction "V+_8") (pintype "power_in"))
      (node (ref "U5") (pin "8") (pinfunction "V+_8") (pintype "power_in"))
    )
    (net (code "63") (name "V-") (class "Default")
      (node (ref "C14") (pin "2") (pinfunction "2_2") (pintype "passive"))
      (node (ref "C15") (pin "2") (pinfunction "2_2") (pintype "passive"))
      (node (ref "C16") (pin "2") (pinfunction "2_2") (pintype "passive"))
      (node (ref "C18") (pin "2") (pinfunction "2_2") (pintype "passive"))
      (node (ref "C19") (pin "2") (pinfunction "2_2") (pintype "passive"))
      (node (ref "C2") (pin "1") (pinfunction "1_1") (pintype "passive"))
      (node (ref "C20") (pin "2") (pinfunction "2_2") (pintype "passive"))
      (node (ref "C21") (pin "1") (pinfunction "1_1") (pintype "passive"))
      (node (ref "C22") (pin "1") (pinfunction "1_1") (pintype "passive"))
      (node (ref "C23") (pin "1") (pinfunction "1_1") (pintype "passive"))
      (node (ref "C24") (pin "1") (pinfunction "1_1") (pintype "passive"))
      (node (ref "C25") (pin "1") (pinfunction "1_1") (pintype "passive"))
      (node (ref "C26") (pin "2") (pinfunction "2_2") (pintype "passive"))
      (node (ref "C27") (pin "2") (pinfunction "2_2") (pintype "passive"))
      (node (ref "C28") (pin "2") (pinfunction "2_2") (pintype "passive"))
      (node (ref "C29") (pin "1") (pinfunction "1_1") (pintype "passive"))
      (node (ref "C30") (pin "1") (pinfunction "1_1") (pintype "passive"))
      (node (ref "C31") (pin "2") (pinfunction "2_2") (pintype "passive"))
      (node (ref "C32") (pin "-") (pinfunction "-_-") (pintype "passive"))
      (node (ref "C33") (pin "-") (pinfunction "-_-") (pintype "passive"))
      (node (ref "C34") (pin "1") (pinfunction "1_1") (pintype "passive"))
      (node (ref "C35") (pin "1") (pinfunction "1_1") (pintype "passive"))
      (node (ref "D1") (pin "A") (pinfunction "A_A") (pintype "passive"))
      (node (ref "J1") (pin "5") (pinfunction "5_5") (pintype "input"))
      (node (ref "JP2") (pin "3") (pinfunction "3_3") (pintype "passive"))
      (node (ref "LED1") (pin "K") (pinfunction "C_K") (pintype "passive"))
      (node (ref "LED2") (pin "K") (pinfunction "C_K") (pintype "passive"))
      (node (ref "LED3") (pin "K") (pinfunction "C_K") (pintype "passive"))
      (node (ref "LED4") (pin "K") (pinfunction "C_K") (pintype "passive"))
      (node (ref "R10") (pin "1") (pinfunction "1_1") (pintype "passive"))
      (node (ref "R27") (pin "2") (pinfunction "2_2") (pintype "passive"))
      (node (ref "R38") (pin "1") (pinfunction "1_1") (pintype "passive"))
      (node (ref "R40") (pin "2") (pinfunction "2_2") (pintype "passive"))
      (node (ref "R41") (pin "1") (pinfunction "1_1") (pintype "passive"))
      (node (ref "S2") (pin "3") (pinfunction "3_3") (pintype "passive"))
      (node (ref "S2") (pin "4") (pinfunction "4_4") (pintype "passive"))
      (node (ref "S3") (pin "3") (pinfunction "3_3") (pintype "passive"))
      (node (ref "S3") (pin "4") (pinfunction "4_4") (pintype "passive"))
      (node (ref "S4") (pin "3") (pinfunction "3_3") (pintype "passive"))
      (node (ref "S4") (pin "4") (pinfunction "4_4") (pintype "passive"))
      (node (ref "U1") (pin "4") (pinfunction "V-_4") (pintype "power_in"))
      (node (ref "U10") (pin "1") (pinfunction "GND_1") (pintype "power_in"))
      (node (ref "U2") (pin "4") (pinfunction "V-_4") (pintype "power_in"))
      (node (ref "U3") (pin "1") (pinfunction "BW_1") (pintype "passive"))
      (node (ref "U3") (pin "4") (pinfunction "V-_4") (pintype "power_in"))
      (node (ref "U4") (pin "4") (pinfunction "V-_4") (pintype "power_in"))
      (node (ref "U5") (pin "4") (pinfunction "V-_4") (pintype "power_in"))
      (node (ref "U6") (pin "23") (pinfunction "VSSSD/VREFSD_23") (pintype "power_in"))
      (node (ref "U6") (pin "47") (pinfunction "VSS_1_47") (pintype "power_in"))
      (node (ref "U6") (pin "8") (pinfunction "VSSA/VREFVDDA/_8") (pintype "power_in"))
      (node (ref "U7") (pin "GND") (pinfunction "GND_GND") (pintype "bidirectional"))
      (node (ref "U8") (pin "10") (pinfunction "SW2_10") (pintype "output"))
      (node (ref "U8") (pin "6") (pinfunction "GND_6") (pintype "power_in"))
      (node (ref "U9") (pin "1") (pinfunction "SHDN_1") (pintype "bidirectional"))
      (node (ref "U9") (pin "5") (pinfunction "GND1_5") (pintype "bidirectional"))
      (node (ref "U9") (pin "6") (pinfunction "GND2_6") (pintype "bidirectional"))
      (node (ref "U9") (pin "7") (pinfunction "GND3_7") (pintype "bidirectional"))
      (node (ref "U9") (pin "8") (pinfunction "GND4_8") (pintype "bidirectional"))
      (node (ref "X1") (pin "1") (pinfunction "P$1_1") (pintype "bidirectional"))
    )
    (net (code "64") (name "VBAT") (class "Default")
      (node (ref "C32") (pin "+") (pinfunction "+_+") (pintype "passive"))
      (node (ref "C35") (pin "2") (pinfunction "2_2") (pintype "passive"))
      (node (ref "R44") (pin "1") (pinfunction "1_1") (pintype "passive"))
      (node (ref "S1") (pin "1") (pinfunction "O_1") (pintype "passive"))
      (node (ref "U10") (pin "3") (pinfunction "VIN_3") (pintype "input"))
      (node (ref "U9") (pin "2") (pinfunction "IN_2") (pintype "bidirectional"))
    )
    (net (code "65") (name "VGND") (class "Default")
      (node (ref "C10") (pin "2") (pinfunction "2_2") (pintype "passive"))
      (node (ref "C11") (pin "2") (pinfunction "2_2") (pintype "passive"))
      (node (ref "C12") (pin "2") (pinfunction "2_2") (pintype "passive"))
      (node (ref "C13") (pin "2") (pinfunction "2_2") (pintype "passive"))
      (node (ref "C14") (pin "1") (pinfunction "1_1") (pintype "passive"))
      (node (ref "C15") (pin "1") (pinfunction "1_1") (pintype "passive"))
      (node (ref "C16") (pin "1") (pinfunction "1_1") (pintype "passive"))
      (node (ref "C17") (pin "2") (pinfunction "2_2") (pintype "passive"))
      (node (ref "C18") (pin "1") (pinfunction "1_1") (pintype "passive"))
      (node (ref "C5") (pin "2") (pinfunction "2_2") (pintype "passive"))
      (node (ref "C8") (pin "2") (pinfunction "2_2") (pintype "passive"))
      (node (ref "R11") (pin "2") (pinfunction "2_2") (pintype "passive"))
      (node (ref "R13") (pin "2") (pinfunction "2_2") (pintype "passive"))
      (node (ref "R19") (pin "S") (pinfunction "S_S") (pintype "passive"))
      (node (ref "R8") (pin "1") (pinfunction "1_1") (pintype "passive"))
      (node (ref "U1") (pin "3") (pinfunction "+IN_3") (pintype "input"))
      (node (ref "U2") (pin "5") (pinfunction "REF_5") (pintype "input"))
      (node (ref "U3") (pin "6") (pinfunction "VO_6") (pintype "output"))
      (node (ref "U5") (pin "5") (pinfunction "+IN_5") (pintype "input"))
      (node (ref "U5") (pin "6") (pinfunction "-IN_6") (pintype "input"))
    )
    (net (code "66") (name "unconnected-(J1-Pad1)") (class "Default")
      (node (ref "J1") (pin "1") (pinfunction "1_1") (pintype "input"))
    )
    (net (code "67") (name "unconnected-(R19-PadA)") (class "Default")
      (node (ref "R19") (pin "A") (pinfunction "A_A") (pintype "passive"))
    )
    (net (code "68") (name "unconnected-(S1-S-Pad3)") (class "Default")
      (node (ref "S1") (pin "3") (pinfunction "S_3") (pintype "passive"))
    )
    (net (code "69") (name "unconnected-(U3-NC-Pad2)") (class "Default")
      (node (ref "U3") (pin "2") (pinfunction "NC_2") (pintype "no_connect"))
    )
    (net (code "70") (name "unconnected-(U3-NC_2-Pad5)") (class "Default")
      (node (ref "U3") (pin "5") (pinfunction "NC_2_5") (pintype "no_connect"))
    )
    (net (code "71") (name "unconnected-(U3-NC_3-Pad8)") (class "Default")
      (node (ref "U3") (pin "8") (pinfunction "NC_3_8") (pintype "no_connect"))
    )
    (net (code "72") (name "unconnected-(U5B-OUT-Pad7)") (class "Default")
      (node (ref "U5") (pin "7") (pinfunction "OUT_7") (pintype "output"))
    )
    (net (code "73") (name "unconnected-(U6-PA0-Pad10)") (class "Default")
      (node (ref "U6") (pin "10") (pinfunction "PA0_10") (pintype "bidirectional"))
    )
    (net (code "74") (name "unconnected-(U6-PA8-Pad29)") (class "Default")
      (node (ref "U6") (pin "29") (pinfunction "PA8_29") (pintype "bidirectional"))
    )
    (net (code "75") (name "unconnected-(U6-PA9-Pad30)") (class "Default")
      (node (ref "U6") (pin "30") (pinfunction "PA9_30") (pintype "bidirectional"))
    )
    (net (code "76") (name "unconnected-(U6-PA10-Pad31)") (class "Default")
      (node (ref "U6") (pin "31") (pinfunction "PA10_31") (pintype "bidirectional"))
    )
    (net (code "77") (name "unconnected-(U6-PA15-Pad38)") (class "Default")
      (node (ref "U6") (pin "38") (pinfunction "PA15_38") (pintype "bidirectional"))
    )
    (net (code "78") (name "unconnected-(U6-PB4-Pad40)") (class "Default")
      (node (ref "U6") (pin "40") (pinfunction "PB4_40") (pintype "bidirectional"))
    )
    (net (code "79") (name "unconnected-(U6-PB5-Pad41)") (class "Default")
      (node (ref "U6") (pin "41") (pinfunction "PB5_41") (pintype "bidirectional"))
    )
    (net (code "80") (name "unconnected-(U6-PC13-Pad2)") (class "Default")
      (node (ref "U6") (pin "2") (pinfunction "PC13_2") (pintype "bidirectional"))
    )
    (net (code "81") (name "unconnected-(U6-PC14_-_OSC32_IN-Pad3)") (class "Default")
      (node (ref "U6") (pin "3") (pinfunction "PC14_-_OSC32_IN_3") (pintype "bidirectional"))
    )
    (net (code "82") (name "unconnected-(U6-PC15_-_OSC32_OUT-Pad4)") (class "Default")
      (node (ref "U6") (pin "4") (pinfunction "PC15_-_OSC32_OUT_4") (pintype "bidirectional"))
    )
    (net (code "83") (name "unconnected-(U6-PF6-Pad35)") (class "Default")
      (node (ref "U6") (pin "35") (pinfunction "PF6_35") (pintype "bidirectional"))
    )
    (net (code "84") (name "unconnected-(U6-PF7-Pad36)") (class "Default")
      (node (ref "U6") (pin "36") (pinfunction "PF7_36") (pintype "bidirectional"))
    )
    (net (code "85") (name "unconnected-(U7-PadGPIO0)") (class "Default")
      (node (ref "U7") (pin "GPIO0") (pinfunction "GPIO0_GPIO0") (pintype "bidirectional"))
    )
    (net (code "86") (name "unconnected-(U7-PadGPIO2)") (class "Default")
      (node (ref "U7") (pin "GPIO2") (pinfunction "GPIO2_GPIO2") (pintype "bidirectional"))
    )
    (net (code "87") (name "unconnected-(U8-X_DAT1-Pad8)") (class "Default")
      (node (ref "U8") (pin "8") (pinfunction "X_DAT1_8") (pintype "output"))
    )
    (net (code "88") (name "unconnected-(U8-X_DAT2-Pad1)") (class "Default")
      (node (ref "U8") (pin "1") (pinfunction "X_DAT2_1") (pintype "output"))
    )
    (net (code "89") (name "unconnected-(U10-TAB-Pad4)") (class "Default")
      (node (ref "U10") (pin "4") (pinfunction "TAB_4") (pintype "no_connect"))
    )
    (net (code "90") (name "{slash}RST") (class "Default")
      (node (ref "JP2") (pin "5") (pinfunction "5_5") (pintype "passive"))
      (node (ref "R37") (pin "1") (pinfunction "1_1") (pintype "passive"))
      (node (ref "U6") (pin "7") (pinfunction "NRST_7") (pintype "passive"))
    )
  )
)
